# Digital_Praytime_Display_P4_75_v0_9.net
KiCad netlist of a schematic drawn in EAGLE
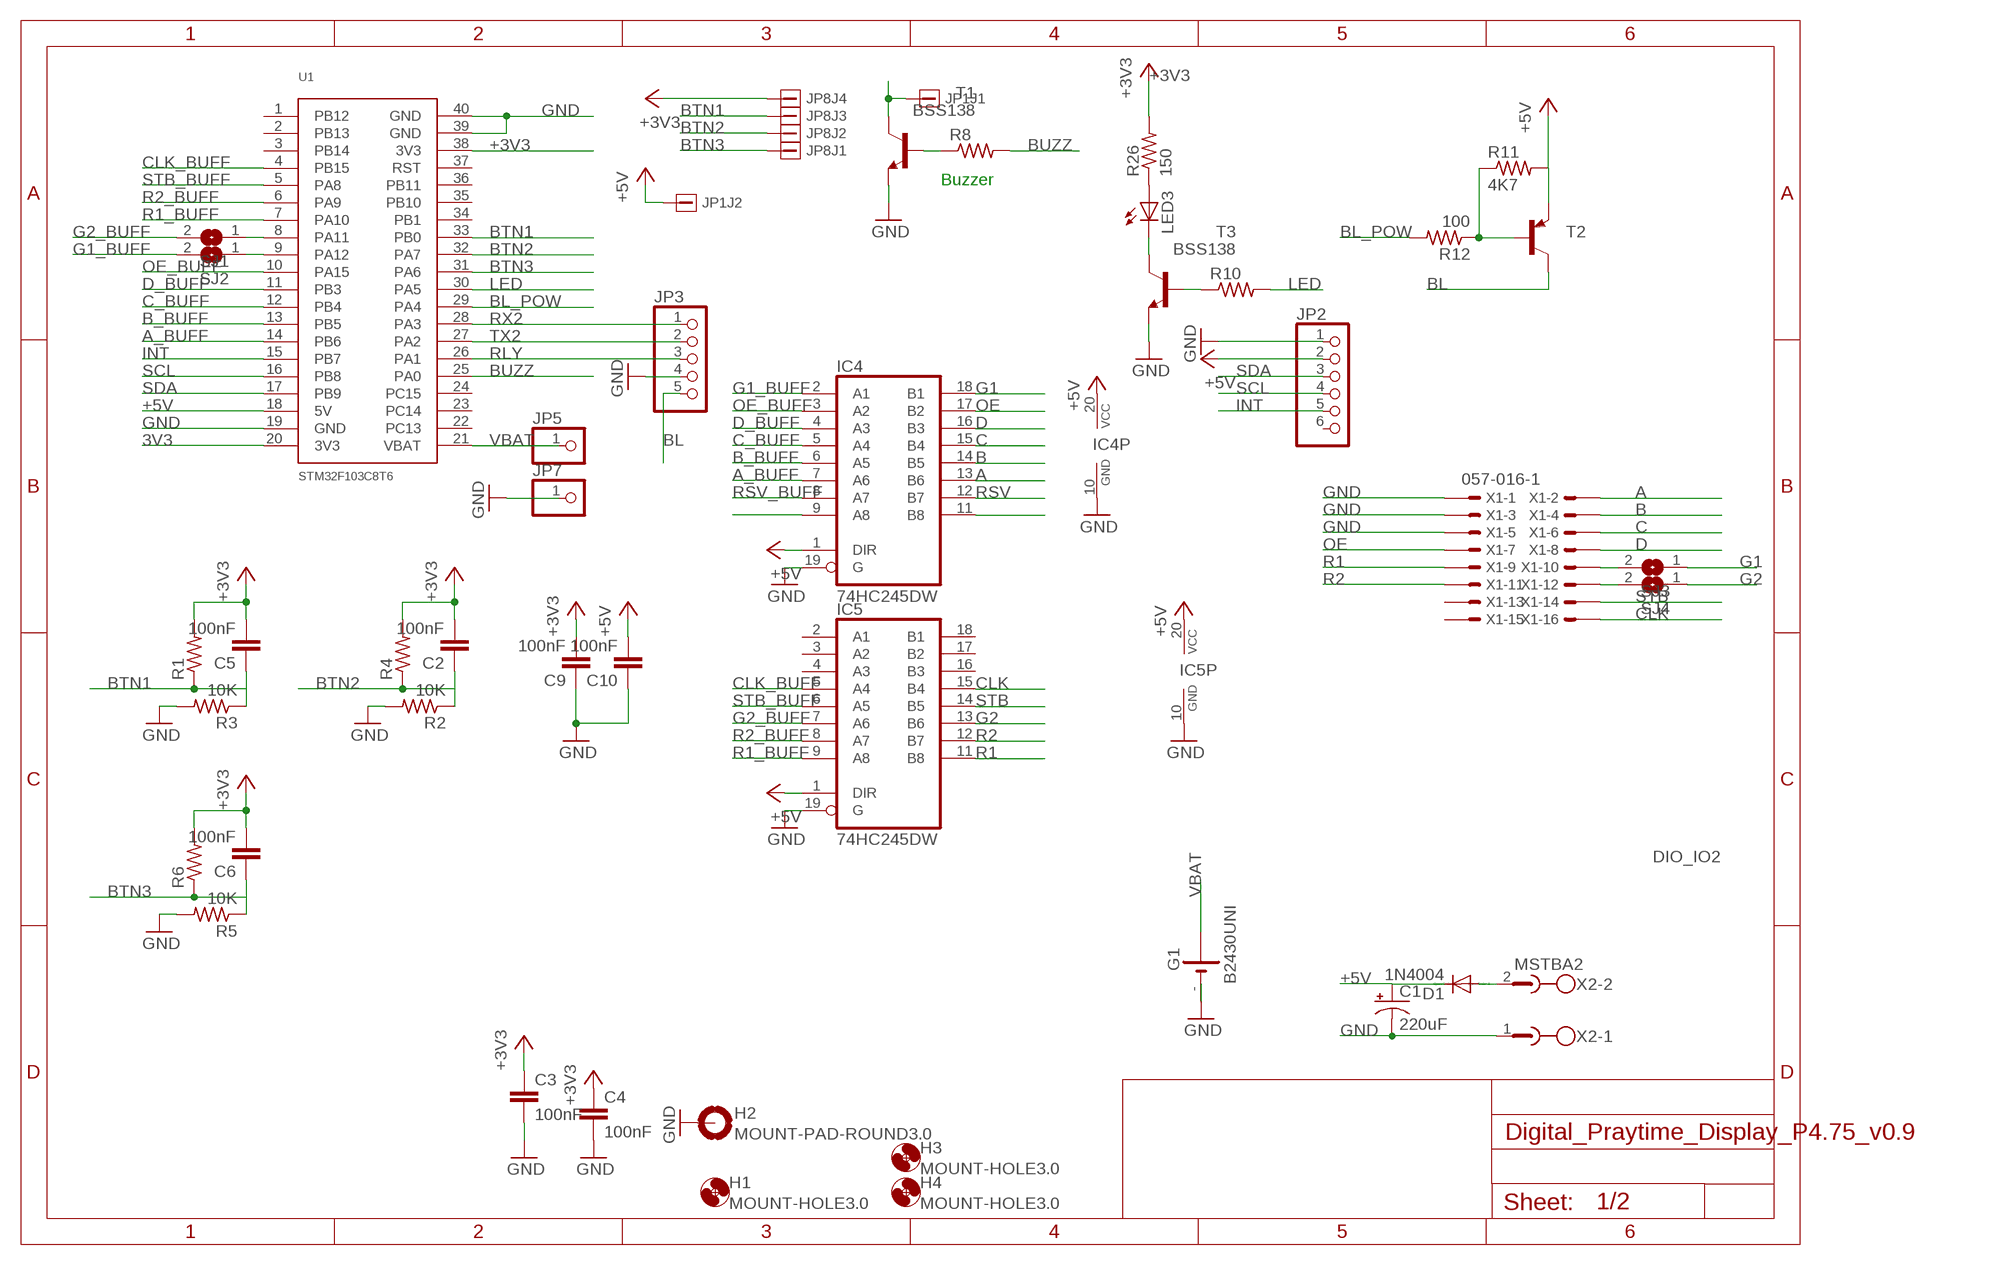
[diagram p0: schematic, sheet 1]
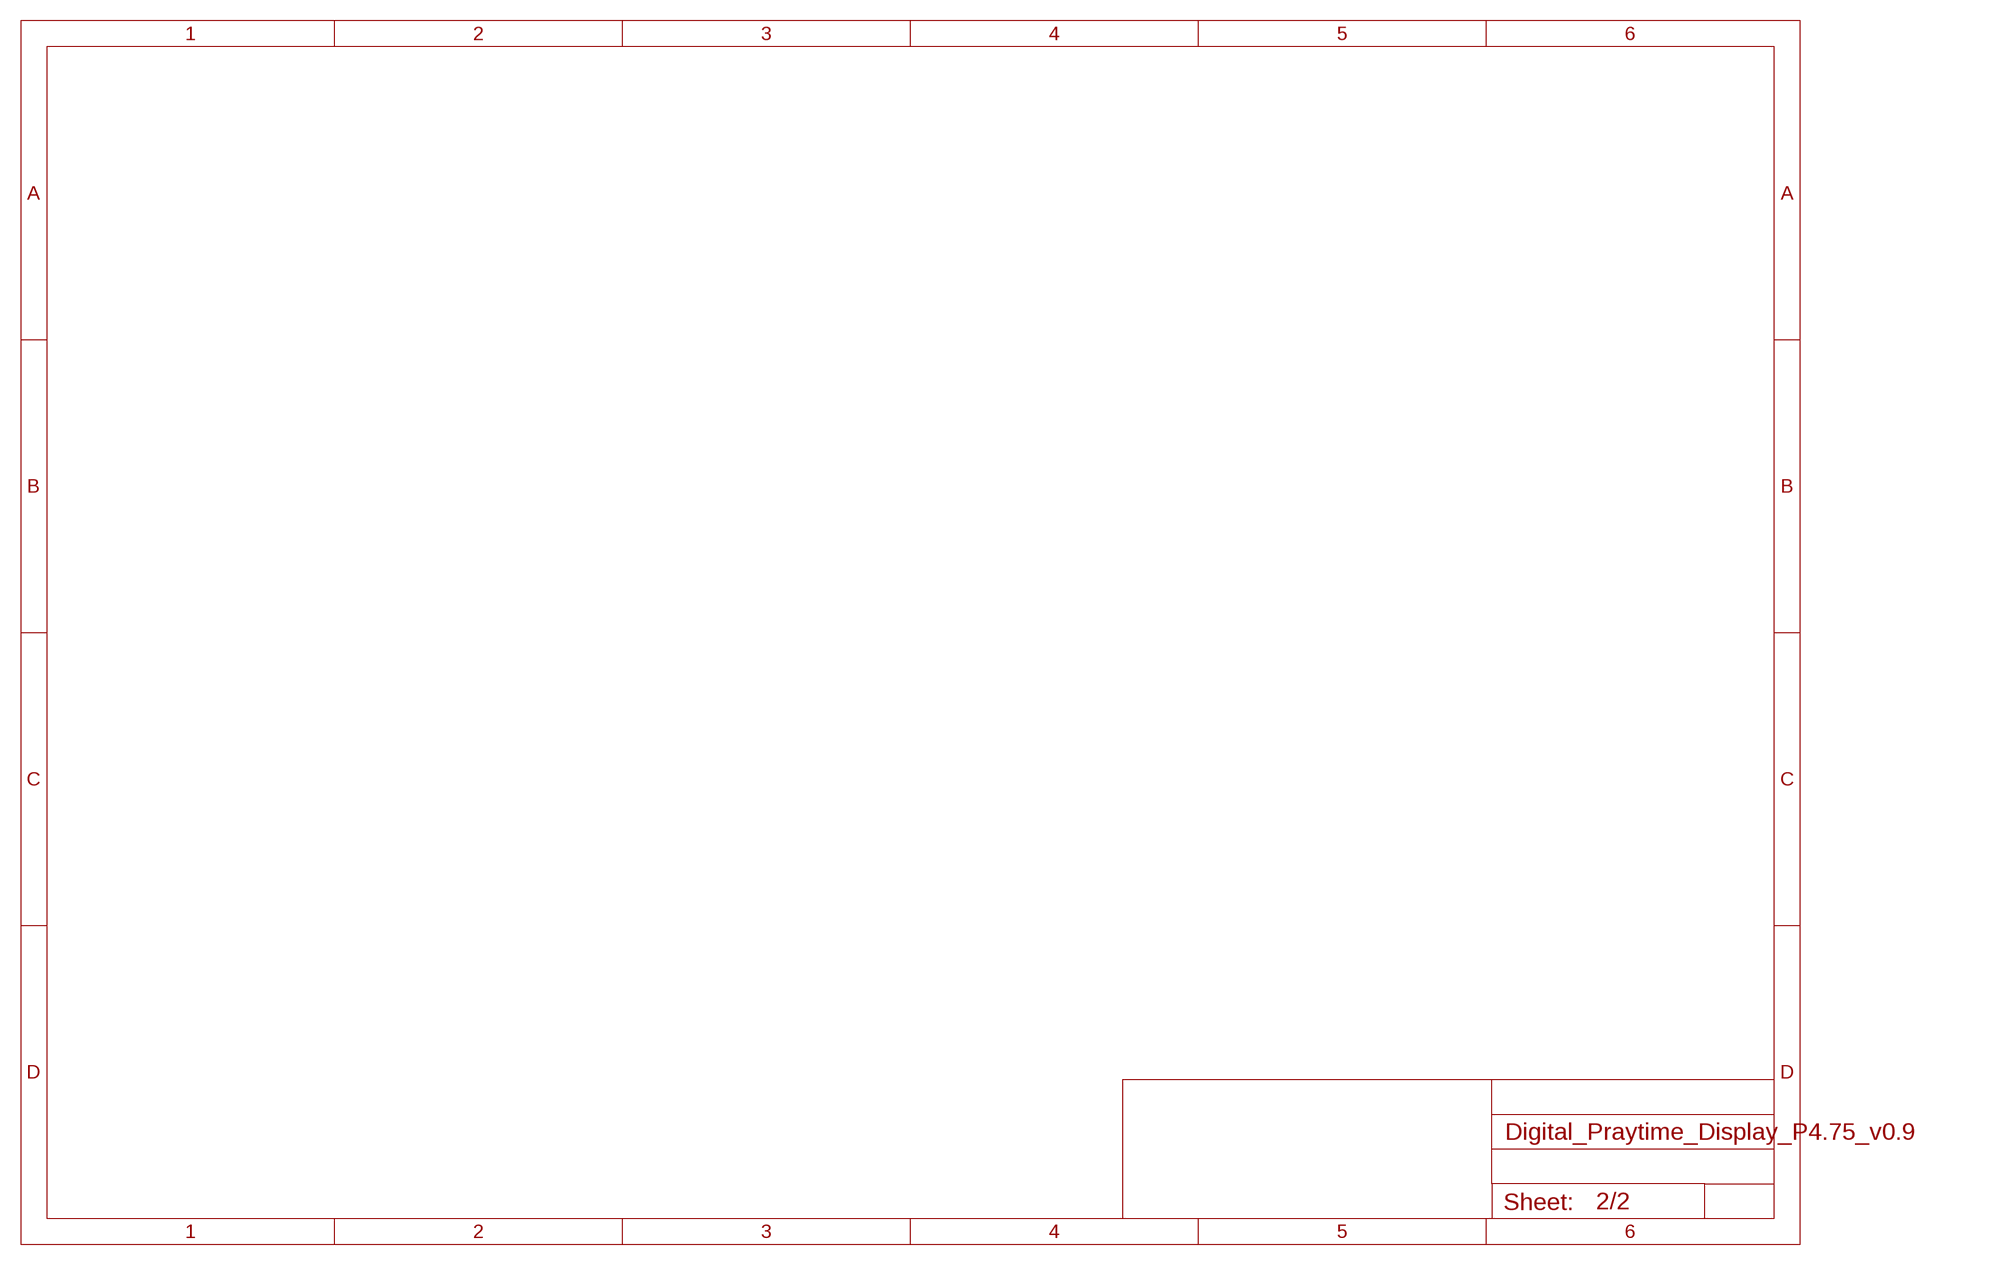
[diagram p1: schematic, sheet 2]

(export (version "E")
  (design (tool "Eeschema 10.0.6"))
  (components
    (comp (ref "C1")
      (value "220uF")
      (footprint "eagle-import:E3,5-8")
      (libsource (lib "eagle-import") (part "CPOL-USE3.5-8"))
    )
    (comp (ref "C2")
      (value "100nF")
      (footprint "eagle-import:C0805")
      (libsource (lib "eagle-import") (part "resistor_C-EUC0805"))
    )
    (comp (ref "C3")
      (value "100nF")
      (footprint "eagle-import:C0805")
      (libsource (lib "eagle-import") (part "C-EUC0805"))
    )
    (comp (ref "C4")
      (value "100nF")
      (footprint "eagle-import:C0805")
      (libsource (lib "eagle-import") (part "C-EUC0805"))
    )
    (comp (ref "C5")
      (value "100nF")
      (footprint "eagle-import:C0805")
      (libsource (lib "eagle-import") (part "resistor_C-EUC0805"))
    )
    (comp (ref "C6")
      (value "100nF")
      (footprint "eagle-import:C0805")
      (libsource (lib "eagle-import") (part "resistor_C-EUC0805"))
    )
    (comp (ref "C9")
      (value "100nF")
      (footprint "eagle-import:C0805")
      (libsource (lib "eagle-import") (part "resistor_C-EUC0805"))
    )
    (comp (ref "C10")
      (value "100nF")
      (footprint "eagle-import:C0805")
      (libsource (lib "eagle-import") (part "resistor_C-EUC0805"))
    )
    (comp (ref "D1")
      (value "1N4004")
      (footprint "eagle-import:DO41-10")
      (libsource (lib "eagle-import") (part "1N4004"))
    )
    (comp (ref "G1")
      (value "B2430UNI")
      (footprint "eagle-import:B2430UNI")
      (libsource (lib "eagle-import") (part "B2430UNI"))
    )
    (comp (ref "H1")
      (value "MOUNT-HOLE3.0")
      (footprint "eagle-import:3,0")
      (libsource (lib "eagle-import") (part "MOUNT-HOLE3.0"))
    )
    (comp (ref "H2")
      (value "MOUNT-PAD-ROUND3.0")
      (footprint "eagle-import:3,0-PAD")
      (libsource (lib "eagle-import") (part "MOUNT-PAD-ROUND3.0"))
    )
    (comp (ref "H3")
      (value "MOUNT-HOLE3.0")
      (footprint "eagle-import:3,0")
      (libsource (lib "eagle-import") (part "MOUNT-HOLE3.0"))
    )
    (comp (ref "H4")
      (value "MOUNT-HOLE3.0")
      (footprint "eagle-import:3,0")
      (libsource (lib "eagle-import") (part "MOUNT-HOLE3.0"))
    )
    (comp (ref "IC4")
      (value "74HC245DW")
      (footprint "eagle-import:SO20W")
      (libsource (lib "eagle-import") (part "74245DWHC"))
    )
    (comp (ref "IC5")
      (value "74HC245DW")
      (footprint "eagle-import:SO20W")
      (libsource (lib "eagle-import") (part "74245DWHC"))
    )
    (comp (ref "JP1")
      (value "CON2-3.81")
      (footprint "eagle-import:CON2-3.81")
      (libsource (lib "eagle-import") (part "CON2-3.81"))
    )
    (comp (ref "JP2")
      (value "PINHD-1X6")
      (footprint "eagle-import:1X06")
      (libsource (lib "eagle-import") (part "PINHD-1X6"))
    )
    (comp (ref "JP3")
      (value "PINHD-1X5")
      (footprint "eagle-import:1X05")
      (libsource (lib "eagle-import") (part "PINHD-1X5"))
    )
    (comp (ref "JP5")
      (value "PINHD-1X1")
      (footprint "eagle-import:1X01")
      (libsource (lib "eagle-import") (part "PINHD-1X1"))
    )
    (comp (ref "JP7")
      (value "PINHD-1X1")
      (footprint "eagle-import:1X01")
      (libsource (lib "eagle-import") (part "PINHD-1X1"))
    )
    (comp (ref "JP8")
      (value "CON4-3.81")
      (footprint "eagle-import:CON4-3.81")
      (libsource (lib "eagle-import") (part "CON4-3.81"))
    )
    (comp (ref "LED3")
      (value "LED3MM")
      (footprint "eagle-import:LED3MM")
      (libsource (lib "eagle-import") (part "LED3MM"))
    )
    (comp (ref "R1")
      (value "R-US_0204/2V")
      (footprint "eagle-import:0204V")
      (libsource (lib "eagle-import") (part "rcl_334_R-US_0204/2V"))
    )
    (comp (ref "R2")
      (value "10K")
      (footprint "eagle-import:M0805")
      (libsource (lib "eagle-import") (part "R-US_M0805"))
    )
    (comp (ref "R3")
      (value "10K")
      (footprint "eagle-import:M0805")
      (libsource (lib "eagle-import") (part "R-US_M0805"))
    )
    (comp (ref "R4")
      (value "R-US_0204/2V")
      (footprint "eagle-import:0204V")
      (libsource (lib "eagle-import") (part "rcl_334_R-US_0204/2V"))
    )
    (comp (ref "R5")
      (value "10K")
      (footprint "eagle-import:M0805")
      (libsource (lib "eagle-import") (part "R-US_M0805"))
    )
    (comp (ref "R6")
      (value "R-US_0204/2V")
      (footprint "eagle-import:0204V")
      (libsource (lib "eagle-import") (part "rcl_334_R-US_0204/2V"))
    )
    (comp (ref "R8")
      (value "R-US_R0805")
      (footprint "eagle-import:R0805")
      (libsource (lib "eagle-import") (part "R-US_R0805"))
    )
    (comp (ref "R10")
      (value "R-US_R0805")
      (footprint "eagle-import:R0805")
      (libsource (lib "eagle-import") (part "R-US_R0805"))
    )
    (comp (ref "R11")
      (value "4K7")
      (footprint "eagle-import:R0805")
      (libsource (lib "eagle-import") (part "R-US_R0805"))
    )
    (comp (ref "R12")
      (value "100")
      (footprint "eagle-import:R0805")
      (libsource (lib "eagle-import") (part "R-US_R0805"))
    )
    (comp (ref "R26")
      (value "150")
      (footprint "eagle-import:R0805")
      (libsource (lib "eagle-import") (part "R-US_R0805"))
    )
    (comp (ref "SJ1") (value "SJ") (footprint "eagle-import:SJ") (libsource (lib "eagle-import") (part "SJ")))
    (comp (ref "SJ2") (value "SJ") (footprint "eagle-import:SJ") (libsource (lib "eagle-import") (part "SJ")))
    (comp (ref "SJ3") (value "SJ") (footprint "eagle-import:SJ") (libsource (lib "eagle-import") (part "SJ")))
    (comp (ref "SJ4") (value "SJ") (footprint "eagle-import:SJ") (libsource (lib "eagle-import") (part "SJ")))
    (comp (ref "T1")
      (value "BSS138")
      (footprint "eagle-import:SOT23-BEC")
      (libsource (lib "eagle-import") (part "-NPN-SOT23-BECMMBT2222ALT1"))
    )
    (comp (ref "T2")
      (value "-PNP-TO126V")
      (footprint "eagle-import:TO126V")
      (libsource (lib "eagle-import") (part "-PNP-TO126V"))
    )
    (comp (ref "T3")
      (value "BSS138")
      (footprint "eagle-import:SOT23-BEC")
      (libsource (lib "eagle-import") (part "-NPN-SOT23-BECMMBT2222ALT1"))
    )
    (comp (ref "U1")
      (value "STM32F103C8T6")
      (footprint "eagle-import:STM32F103")
      (libsource (lib "eagle-import") (part "STM32F103C8T6"))
    )
    (comp (ref "X1")
      (value "057-016-1")
      (footprint "eagle-import:057-016-1")
      (libsource (lib "eagle-import") (part "057-016-1"))
    )
    (comp (ref "X2")
      (value "MSTBA2")
      (footprint "eagle-import:MSTBA2")
      (fields (field (name "MF") "FARNELL") (field (name "MPN") "1757242"))
      (libsource (lib "eagle-import") (part "MSTBA2"))
    )
  )
  (nets
    (net (code "1") (name "+3V3") (class "Default")
      (node (ref "C2") (pin "2") (pinfunction "2_2") (pintype "passive"))
      (node (ref "C3") (pin "1") (pinfunction "1_1") (pintype "passive"))
      (node (ref "C4") (pin "1") (pinfunction "1_1") (pintype "passive"))
      (node (ref "C5") (pin "2") (pinfunction "2_2") (pintype "passive"))
      (node (ref "C6") (pin "2") (pinfunction "2_2") (pintype "passive"))
      (node (ref "C9") (pin "2") (pinfunction "2_2") (pintype "passive"))
      (node (ref "JP8") (pin "4") (pinfunction "1_4") (pintype "passive"))
      (node (ref "R1") (pin "2") (pinfunction "2_2") (pintype "passive"))
      (node (ref "R26") (pin "2") (pinfunction "2_2") (pintype "passive"))
      (node (ref "R4") (pin "2") (pinfunction "2_2") (pintype "passive"))
      (node (ref "R6") (pin "2") (pinfunction "2_2") (pintype "passive"))
      (node (ref "U1") (pin "38") (pinfunction "3V3_38") (pintype "bidirectional"))
    )
    (net (code "2") (name "+5V") (class "Default")
      (node (ref "C1") (pin "+") (pinfunction "+_+") (pintype "passive"))
      (node (ref "C10") (pin "2") (pinfunction "2_2") (pintype "passive"))
      (node (ref "D1") (pin "C") (pinfunction "C_C") (pintype "passive"))
      (node (ref "IC4") (pin "1") (pinfunction "DIR_1") (pintype "input"))
      (node (ref "IC4") (pin "20") (pinfunction "VCC_20") (pintype "power_in"))
      (node (ref "IC5") (pin "1") (pinfunction "DIR_1") (pintype "input"))
      (node (ref "IC5") (pin "20") (pinfunction "VCC_20") (pintype "power_in"))
      (node (ref "JP1") (pin "2") (pinfunction "1_2") (pintype "passive"))
      (node (ref "JP2") (pin "2") (pinfunction "2_2") (pintype "passive"))
      (node (ref "R11") (pin "2") (pinfunction "2_2") (pintype "passive"))
      (node (ref "T2") (pin "1") (pinfunction "E_1") (pintype "passive"))
      (node (ref "U1") (pin "18") (pinfunction "5V_18") (pintype "bidirectional"))
    )
    (net (code "3") (name "3V3") (class "Default")
      (node (ref "U1") (pin "20") (pinfunction "3V3_20") (pintype "bidirectional"))
    )
    (net (code "4") (name "A") (class "Default")
      (node (ref "IC4") (pin "13") (pinfunction "B6_13") (pintype "bidirectional"))
      (node (ref "X1") (pin "2") (pinfunction "S_2") (pintype "passive"))
    )
    (net (code "5") (name "A_BUFF") (class "Default")
      (node (ref "IC4") (pin "7") (pinfunction "A6_7") (pintype "bidirectional"))
      (node (ref "U1") (pin "14") (pinfunction "PB6_14") (pintype "bidirectional"))
    )
    (net (code "6") (name "B") (class "Default")
      (node (ref "IC4") (pin "14") (pinfunction "B5_14") (pintype "bidirectional"))
      (node (ref "X1") (pin "4") (pinfunction "S_4") (pintype "passive"))
    )
    (net (code "7") (name "BL") (class "Default")
      (node (ref "JP3") (pin "5") (pinfunction "5_5") (pintype "passive"))
      (node (ref "T2") (pin "2") (pinfunction "C_2") (pintype "passive"))
    )
    (net (code "8") (name "BL_POW") (class "Default")
      (node (ref "R12") (pin "2") (pinfunction "2_2") (pintype "passive"))
      (node (ref "U1") (pin "29") (pinfunction "PA4_29") (pintype "bidirectional"))
    )
    (net (code "9") (name "BTN1") (class "Default")
      (node (ref "C5") (pin "1") (pinfunction "1_1") (pintype "passive"))
      (node (ref "JP8") (pin "3") (pinfunction "1_3") (pintype "passive"))
      (node (ref "R1") (pin "1") (pinfunction "1_1") (pintype "passive"))
      (node (ref "R3") (pin "1") (pinfunction "1_1") (pintype "passive"))
      (node (ref "U1") (pin "33") (pinfunction "PB0_33") (pintype "bidirectional"))
    )
    (net (code "10") (name "BTN2") (class "Default")
      (node (ref "C2") (pin "1") (pinfunction "1_1") (pintype "passive"))
      (node (ref "JP8") (pin "2") (pinfunction "1_2") (pintype "passive"))
      (node (ref "R2") (pin "1") (pinfunction "1_1") (pintype "passive"))
      (node (ref "R4") (pin "1") (pinfunction "1_1") (pintype "passive"))
      (node (ref "U1") (pin "32") (pinfunction "PA7_32") (pintype "bidirectional"))
    )
    (net (code "11") (name "BTN3") (class "Default")
      (node (ref "C6") (pin "1") (pinfunction "1_1") (pintype "passive"))
      (node (ref "JP8") (pin "1") (pinfunction "1_1") (pintype "passive"))
      (node (ref "R5") (pin "1") (pinfunction "1_1") (pintype "passive"))
      (node (ref "R6") (pin "1") (pinfunction "1_1") (pintype "passive"))
      (node (ref "U1") (pin "31") (pinfunction "PA6_31") (pintype "bidirectional"))
    )
    (net (code "12") (name "BUZZ") (class "Default")
      (node (ref "R8") (pin "2") (pinfunction "2_2") (pintype "passive"))
      (node (ref "U1") (pin "25") (pinfunction "PA0_25") (pintype "bidirectional"))
    )
    (net (code "13") (name "B_BUFF") (class "Default")
      (node (ref "IC4") (pin "6") (pinfunction "A5_6") (pintype "bidirectional"))
      (node (ref "U1") (pin "13") (pinfunction "PB5_13") (pintype "bidirectional"))
    )
    (net (code "14") (name "C") (class "Default")
      (node (ref "IC4") (pin "15") (pinfunction "B4_15") (pintype "bidirectional"))
      (node (ref "X1") (pin "6") (pinfunction "S_6") (pintype "passive"))
    )
    (net (code "15") (name "CLK") (class "Default")
      (node (ref "IC5") (pin "15") (pinfunction "B4_15") (pintype "bidirectional"))
      (node (ref "X1") (pin "16") (pinfunction "S_16") (pintype "passive"))
    )
    (net (code "16") (name "CLK_BUFF") (class "Default")
      (node (ref "IC5") (pin "5") (pinfunction "A4_5") (pintype "bidirectional"))
      (node (ref "U1") (pin "4") (pinfunction "PB15_4") (pintype "bidirectional"))
    )
    (net (code "17") (name "C_BUFF") (class "Default")
      (node (ref "IC4") (pin "5") (pinfunction "A4_5") (pintype "bidirectional"))
      (node (ref "U1") (pin "12") (pinfunction "PB4_12") (pintype "bidirectional"))
    )
    (net (code "18") (name "D") (class "Default")
      (node (ref "IC4") (pin "16") (pinfunction "B3_16") (pintype "bidirectional"))
      (node (ref "X1") (pin "8") (pinfunction "S_8") (pintype "passive"))
    )
    (net (code "20") (name "D_BUFF") (class "Default")
      (node (ref "IC4") (pin "4") (pinfunction "A3_4") (pintype "bidirectional"))
      (node (ref "U1") (pin "11") (pinfunction "PB3_11") (pintype "bidirectional"))
    )
    (net (code "21") (name "G1") (class "Default")
      (node (ref "IC4") (pin "18") (pinfunction "B1_18") (pintype "bidirectional"))
      (node (ref "SJ3") (pin "1") (pinfunction "1_1") (pintype "passive"))
    )
    (net (code "22") (name "G1_BUFF") (class "Default")
      (node (ref "IC4") (pin "2") (pinfunction "A1_2") (pintype "bidirectional"))
      (node (ref "SJ2") (pin "2") (pinfunction "2_2") (pintype "passive"))
    )
    (net (code "23") (name "G2") (class "Default")
      (node (ref "IC5") (pin "13") (pinfunction "B6_13") (pintype "bidirectional"))
      (node (ref "SJ4") (pin "1") (pinfunction "1_1") (pintype "passive"))
    )
    (net (code "24") (name "G2_BUFF") (class "Default")
      (node (ref "IC5") (pin "7") (pinfunction "A6_7") (pintype "bidirectional"))
      (node (ref "SJ1") (pin "2") (pinfunction "2_2") (pintype "passive"))
    )
    (net (code "25") (name "GND") (class "Default")
      (node (ref "C1") (pin "-") (pinfunction "-_-") (pintype "passive"))
      (node (ref "C10") (pin "1") (pinfunction "1_1") (pintype "passive"))
      (node (ref "C3") (pin "2") (pinfunction "2_2") (pintype "passive"))
      (node (ref "C4") (pin "2") (pinfunction "2_2") (pintype "passive"))
      (node (ref "C9") (pin "1") (pinfunction "1_1") (pintype "passive"))
      (node (ref "G1") (pin "-") (pinfunction "-_-") (pintype "passive"))
      (node (ref "G1") (pin "-@1") (pinfunction "-_-@1") (pintype "passive"))
      (node (ref "H2") (pin "B3,0") (pinfunction "MOUNT_B3,0") (pintype "passive"))
      (node (ref "IC4") (pin "10") (pinfunction "GND_10") (pintype "power_in"))
      (node (ref "IC4") (pin "19") (pinfunction "G_19") (pintype "input"))
      (node (ref "IC5") (pin "10") (pinfunction "GND_10") (pintype "power_in"))
      (node (ref "IC5") (pin "19") (pinfunction "G_19") (pintype "input"))
      (node (ref "JP2") (pin "1") (pinfunction "1_1") (pintype "passive"))
      (node (ref "JP3") (pin "4") (pinfunction "4_4") (pintype "passive"))
      (node (ref "JP7") (pin "1") (pinfunction "1_1") (pintype "passive"))
      (node (ref "R2") (pin "2") (pinfunction "2_2") (pintype "passive"))
      (node (ref "R3") (pin "2") (pinfunction "2_2") (pintype "passive"))
      (node (ref "R5") (pin "2") (pinfunction "2_2") (pintype "passive"))
      (node (ref "T1") (pin "E") (pinfunction "E_E") (pintype "passive"))
      (node (ref "T3") (pin "E") (pinfunction "E_E") (pintype "passive"))
      (node (ref "U1") (pin "19") (pinfunction "GND_19") (pintype "bidirectional"))
      (node (ref "U1") (pin "39") (pinfunction "GND_39") (pintype "bidirectional"))
      (node (ref "U1") (pin "40") (pinfunction "GND_40") (pintype "bidirectional"))
      (node (ref "X1") (pin "1") (pinfunction "S_1") (pintype "passive"))
      (node (ref "X1") (pin "3") (pinfunction "S_3") (pintype "passive"))
      (node (ref "X1") (pin "5") (pinfunction "S_5") (pintype "passive"))
      (node (ref "X2") (pin "1") (pinfunction "1_1") (pintype "passive"))
    )
    (net (code "26") (name "INT") (class "Default")
      (node (ref "JP2") (pin "5") (pinfunction "5_5") (pintype "passive"))
      (node (ref "U1") (pin "15") (pinfunction "PB7_15") (pintype "bidirectional"))
    )
    (net (code "27") (name "LED") (class "Default")
      (node (ref "R10") (pin "2") (pinfunction "2_2") (pintype "passive"))
      (node (ref "U1") (pin "30") (pinfunction "PA5_30") (pintype "bidirectional"))
    )
    (net (code "28") (name "Net-(JP1-Pad1)") (class "Default")
      (node (ref "JP1") (pin "1") (pinfunction "1_1") (pintype "passive"))
      (node (ref "T1") (pin "C") (pinfunction "C_C") (pintype "passive"))
    )
    (net (code "29") (name "Net-(LED3-C)") (class "Default")
      (node (ref "LED3") (pin "K") (pinfunction "C_K") (pintype "passive"))
      (node (ref "T3") (pin "C") (pinfunction "C_C") (pintype "passive"))
    )
    (net (code "30") (name "Net-(LED3-PadA)") (class "Default")
      (node (ref "LED3") (pin "A") (pinfunction "A_A") (pintype "passive"))
      (node (ref "R26") (pin "1") (pinfunction "1_1") (pintype "passive"))
    )
    (net (code "31") (name "Net-(R8-Pad1)") (class "Default")
      (node (ref "R8") (pin "1") (pinfunction "1_1") (pintype "passive"))
      (node (ref "T1") (pin "B") (pinfunction "B_B") (pintype "passive"))
    )
    (net (code "32") (name "Net-(R10-Pad1)") (class "Default")
      (node (ref "R10") (pin "1") (pinfunction "1_1") (pintype "passive"))
      (node (ref "T3") (pin "B") (pinfunction "B_B") (pintype "passive"))
    )
    (net (code "33") (name "Net-(T2-B)") (class "Default")
      (node (ref "R11") (pin "1") (pinfunction "1_1") (pintype "passive"))
      (node (ref "R12") (pin "1") (pinfunction "1_1") (pintype "passive"))
      (node (ref "T2") (pin "3") (pinfunction "B_3") (pintype "passive"))
    )
    (net (code "34") (name "Net-(U1-PA11)") (class "Default")
      (node (ref "SJ1") (pin "1") (pinfunction "1_1") (pintype "passive"))
      (node (ref "U1") (pin "8") (pinfunction "PA11_8") (pintype "bidirectional"))
    )
    (net (code "35") (name "Net-(U1-PA12)") (class "Default")
      (node (ref "SJ2") (pin "1") (pinfunction "1_1") (pintype "passive"))
      (node (ref "U1") (pin "9") (pinfunction "PA12_9") (pintype "bidirectional"))
    )
    (net (code "36") (name "Net-(X1B-S)") (class "Default")
      (node (ref "SJ3") (pin "2") (pinfunction "2_2") (pintype "passive"))
      (node (ref "X1") (pin "10") (pinfunction "S_10") (pintype "passive"))
    )
    (net (code "37") (name "Net-(X1D-S)") (class "Default")
      (node (ref "SJ4") (pin "2") (pinfunction "2_2") (pintype "passive"))
      (node (ref "X1") (pin "12") (pinfunction "S_12") (pintype "passive"))
    )
    (net (code "38") (name "Net-(X2B-1)") (class "Default")
      (node (ref "D1") (pin "A") (pinfunction "A_A") (pintype "passive"))
      (node (ref "X2") (pin "2") (pinfunction "1_2") (pintype "passive"))
    )
    (net (code "39") (name "OE") (class "Default")
      (node (ref "IC4") (pin "17") (pinfunction "B2_17") (pintype "bidirectional"))
      (node (ref "X1") (pin "7") (pinfunction "S_7") (pintype "passive"))
    )
    (net (code "40") (name "OE_BUFF") (class "Default")
      (node (ref "IC4") (pin "3") (pinfunction "A2_3") (pintype "bidirectional"))
      (node (ref "U1") (pin "10") (pinfunction "PA15_10") (pintype "bidirectional"))
    )
    (net (code "41") (name "R1") (class "Default")
      (node (ref "IC5") (pin "11") (pinfunction "B8_11") (pintype "bidirectional"))
      (node (ref "X1") (pin "9") (pinfunction "S_9") (pintype "passive"))
    )
    (net (code "42") (name "R1_BUFF") (class "Default")
      (node (ref "IC5") (pin "9") (pinfunction "A8_9") (pintype "bidirectional"))
      (node (ref "U1") (pin "7") (pinfunction "PA10_7") (pintype "bidirectional"))
    )
    (net (code "43") (name "R2") (class "Default")
      (node (ref "IC5") (pin "12") (pinfunction "B7_12") (pintype "bidirectional"))
      (node (ref "X1") (pin "11") (pinfunction "S_11") (pintype "passive"))
    )
    (net (code "44") (name "R2_BUFF") (class "Default")
      (node (ref "IC5") (pin "8") (pinfunction "A7_8") (pintype "bidirectional"))
      (node (ref "U1") (pin "6") (pinfunction "PA9_6") (pintype "bidirectional"))
    )
    (net (code "45") (name "RLY") (class "Default")
      (node (ref "JP3") (pin "3") (pinfunction "3_3") (pintype "passive"))
      (node (ref "U1") (pin "26") (pinfunction "PA1_26") (pintype "bidirectional"))
    )
    (net (code "46") (name "RSV") (class "Default")
      (node (ref "IC4") (pin "12") (pinfunction "B7_12") (pintype "bidirectional"))
    )
    (net (code "47") (name "RSV_BUFF") (class "Default")
      (node (ref "IC4") (pin "8") (pinfunction "A7_8") (pintype "bidirectional"))
    )
    (net (code "48") (name "RX2") (class "Default")
      (node (ref "JP3") (pin "1") (pinfunction "1_1") (pintype "passive"))
      (node (ref "U1") (pin "28") (pinfunction "PA3_28") (pintype "bidirectional"))
    )
    (net (code "49") (name "SCL") (class "Default")
      (node (ref "JP2") (pin "4") (pinfunction "4_4") (pintype "passive"))
      (node (ref "U1") (pin "16") (pinfunction "PB8_16") (pintype "bidirectional"))
    )
    (net (code "50") (name "SDA") (class "Default")
      (node (ref "JP2") (pin "3") (pinfunction "3_3") (pintype "passive"))
      (node (ref "U1") (pin "17") (pinfunction "PB9_17") (pintype "bidirectional"))
    )
    (net (code "51") (name "STB") (class "Default")
      (node (ref "IC5") (pin "14") (pinfunction "B5_14") (pintype "bidirectional"))
      (node (ref "X1") (pin "14") (pinfunction "S_14") (pintype "passive"))
    )
    (net (code "52") (name "STB_BUFF") (class "Default")
      (node (ref "IC5") (pin "6") (pinfunction "A5_6") (pintype "bidirectional"))
      (node (ref "U1") (pin "5") (pinfunction "PA8_5") (pintype "bidirectional"))
    )
    (net (code "53") (name "TX2") (class "Default")
      (node (ref "JP3") (pin "2") (pinfunction "2_2") (pintype "passive"))
      (node (ref "U1") (pin "27") (pinfunction "PA2_27") (pintype "bidirectional"))
    )
    (net (code "54") (name "VBAT") (class "Default")
      (node (ref "G1") (pin "+@4") (pinfunction "+_+@4") (pintype "passive"))
      (node (ref "JP5") (pin "1") (pinfunction "1_1") (pintype "passive"))
      (node (ref "U1") (pin "21") (pinfunction "VBAT_21") (pintype "bidirectional"))
    )
    (net (code "55") (name "unconnected-(IC4A-A8-Pad9)") (class "Default")
      (node (ref "IC4") (pin "9") (pinfunction "A8_9") (pintype "bidirectional"))
    )
    (net (code "56") (name "unconnected-(IC4A-B8-Pad11)") (class "Default")
      (node (ref "IC4") (pin "11") (pinfunction "B8_11") (pintype "bidirectional"))
    )
    (net (code "57") (name "unconnected-(IC5A-A1-Pad2)") (class "Default")
      (node (ref "IC5") (pin "2") (pinfunction "A1_2") (pintype "bidirectional"))
    )
    (net (code "58") (name "unconnected-(IC5A-A2-Pad3)") (class "Default")
      (node (ref "IC5") (pin "3") (pinfunction "A2_3") (pintype "bidirectional"))
    )
    (net (code "59") (name "unconnected-(IC5A-A3-Pad4)") (class "Default")
      (node (ref "IC5") (pin "4") (pinfunction "A3_4") (pintype "bidirectional"))
    )
    (net (code "60") (name "unconnected-(IC5A-B1-Pad18)") (class "Default")
      (node (ref "IC5") (pin "18") (pinfunction "B1_18") (pintype "bidirectional"))
    )
    (net (code "61") (name "unconnected-(IC5A-B2-Pad17)") (class "Default")
      (node (ref "IC5") (pin "17") (pinfunction "B2_17") (pintype "bidirectional"))
    )
    (net (code "62") (name "unconnected-(IC5A-B3-Pad16)") (class "Default")
      (node (ref "IC5") (pin "16") (pinfunction "B3_16") (pintype "bidirectional"))
    )
    (net (code "63") (name "unconnected-(JP2-Pad6)") (class "Default")
      (node (ref "JP2") (pin "6") (pinfunction "6_6") (pintype "passive"))
    )
    (net (code "64") (name "unconnected-(U1-PB1-Pad34)") (class "Default")
      (node (ref "U1") (pin "34") (pinfunction "PB1_34") (pintype "bidirectional"))
    )
    (net (code "65") (name "unconnected-(U1-PB10-Pad35)") (class "Default")
      (node (ref "U1") (pin "35") (pinfunction "PB10_35") (pintype "bidirectional"))
    )
    (net (code "66") (name "unconnected-(U1-PB11-Pad36)") (class "Default")
      (node (ref "U1") (pin "36") (pinfunction "PB11_36") (pintype "bidirectional"))
    )
    (net (code "67") (name "unconnected-(U1-PB12-Pad1)") (class "Default")
      (node (ref "U1") (pin "1") (pinfunction "PB12_1") (pintype "bidirectional"))
    )
    (net (code "68") (name "unconnected-(U1-PB13-Pad2)") (class "Default")
      (node (ref "U1") (pin "2") (pinfunction "PB13_2") (pintype "bidirectional"))
    )
    (net (code "69") (name "unconnected-(U1-PB14-Pad3)") (class "Default")
      (node (ref "U1") (pin "3") (pinfunction "PB14_3") (pintype "bidirectional"))
    )
    (net (code "70") (name "unconnected-(U1-PC13-Pad22)") (class "Default")
      (node (ref "U1") (pin "22") (pinfunction "PC13_22") (pintype "bidirectional"))
    )
    (net (code "71") (name "unconnected-(U1-PC14-Pad23)") (class "Default")
      (node (ref "U1") (pin "23") (pinfunction "PC14_23") (pintype "bidirectional"))
    )
    (net (code "72") (name "unconnected-(U1-PC15-Pad24)") (class "Default")
      (node (ref "U1") (pin "24") (pinfunction "PC15_24") (pintype "bidirectional"))
    )
    (net (code "73") (name "unconnected-(U1-RST-Pad37)") (class "Default")
      (node (ref "U1") (pin "37") (pinfunction "RST_37") (pintype "bidirectional"))
    )
    (net (code "74") (name "unconnected-(X1E-S-Pad13)") (class "Default")
      (node (ref "X1") (pin "13") (pinfunction "S_13") (pintype "passive"))
    )
    (net (code "75") (name "unconnected-(X1G-S-Pad15)") (class "Default")
      (node (ref "X1") (pin "15") (pinfunction "S_15") (pintype "passive"))
    )
  )
)
